# FSShield.net
KiCad netlist of a schematic drawn in EAGLE
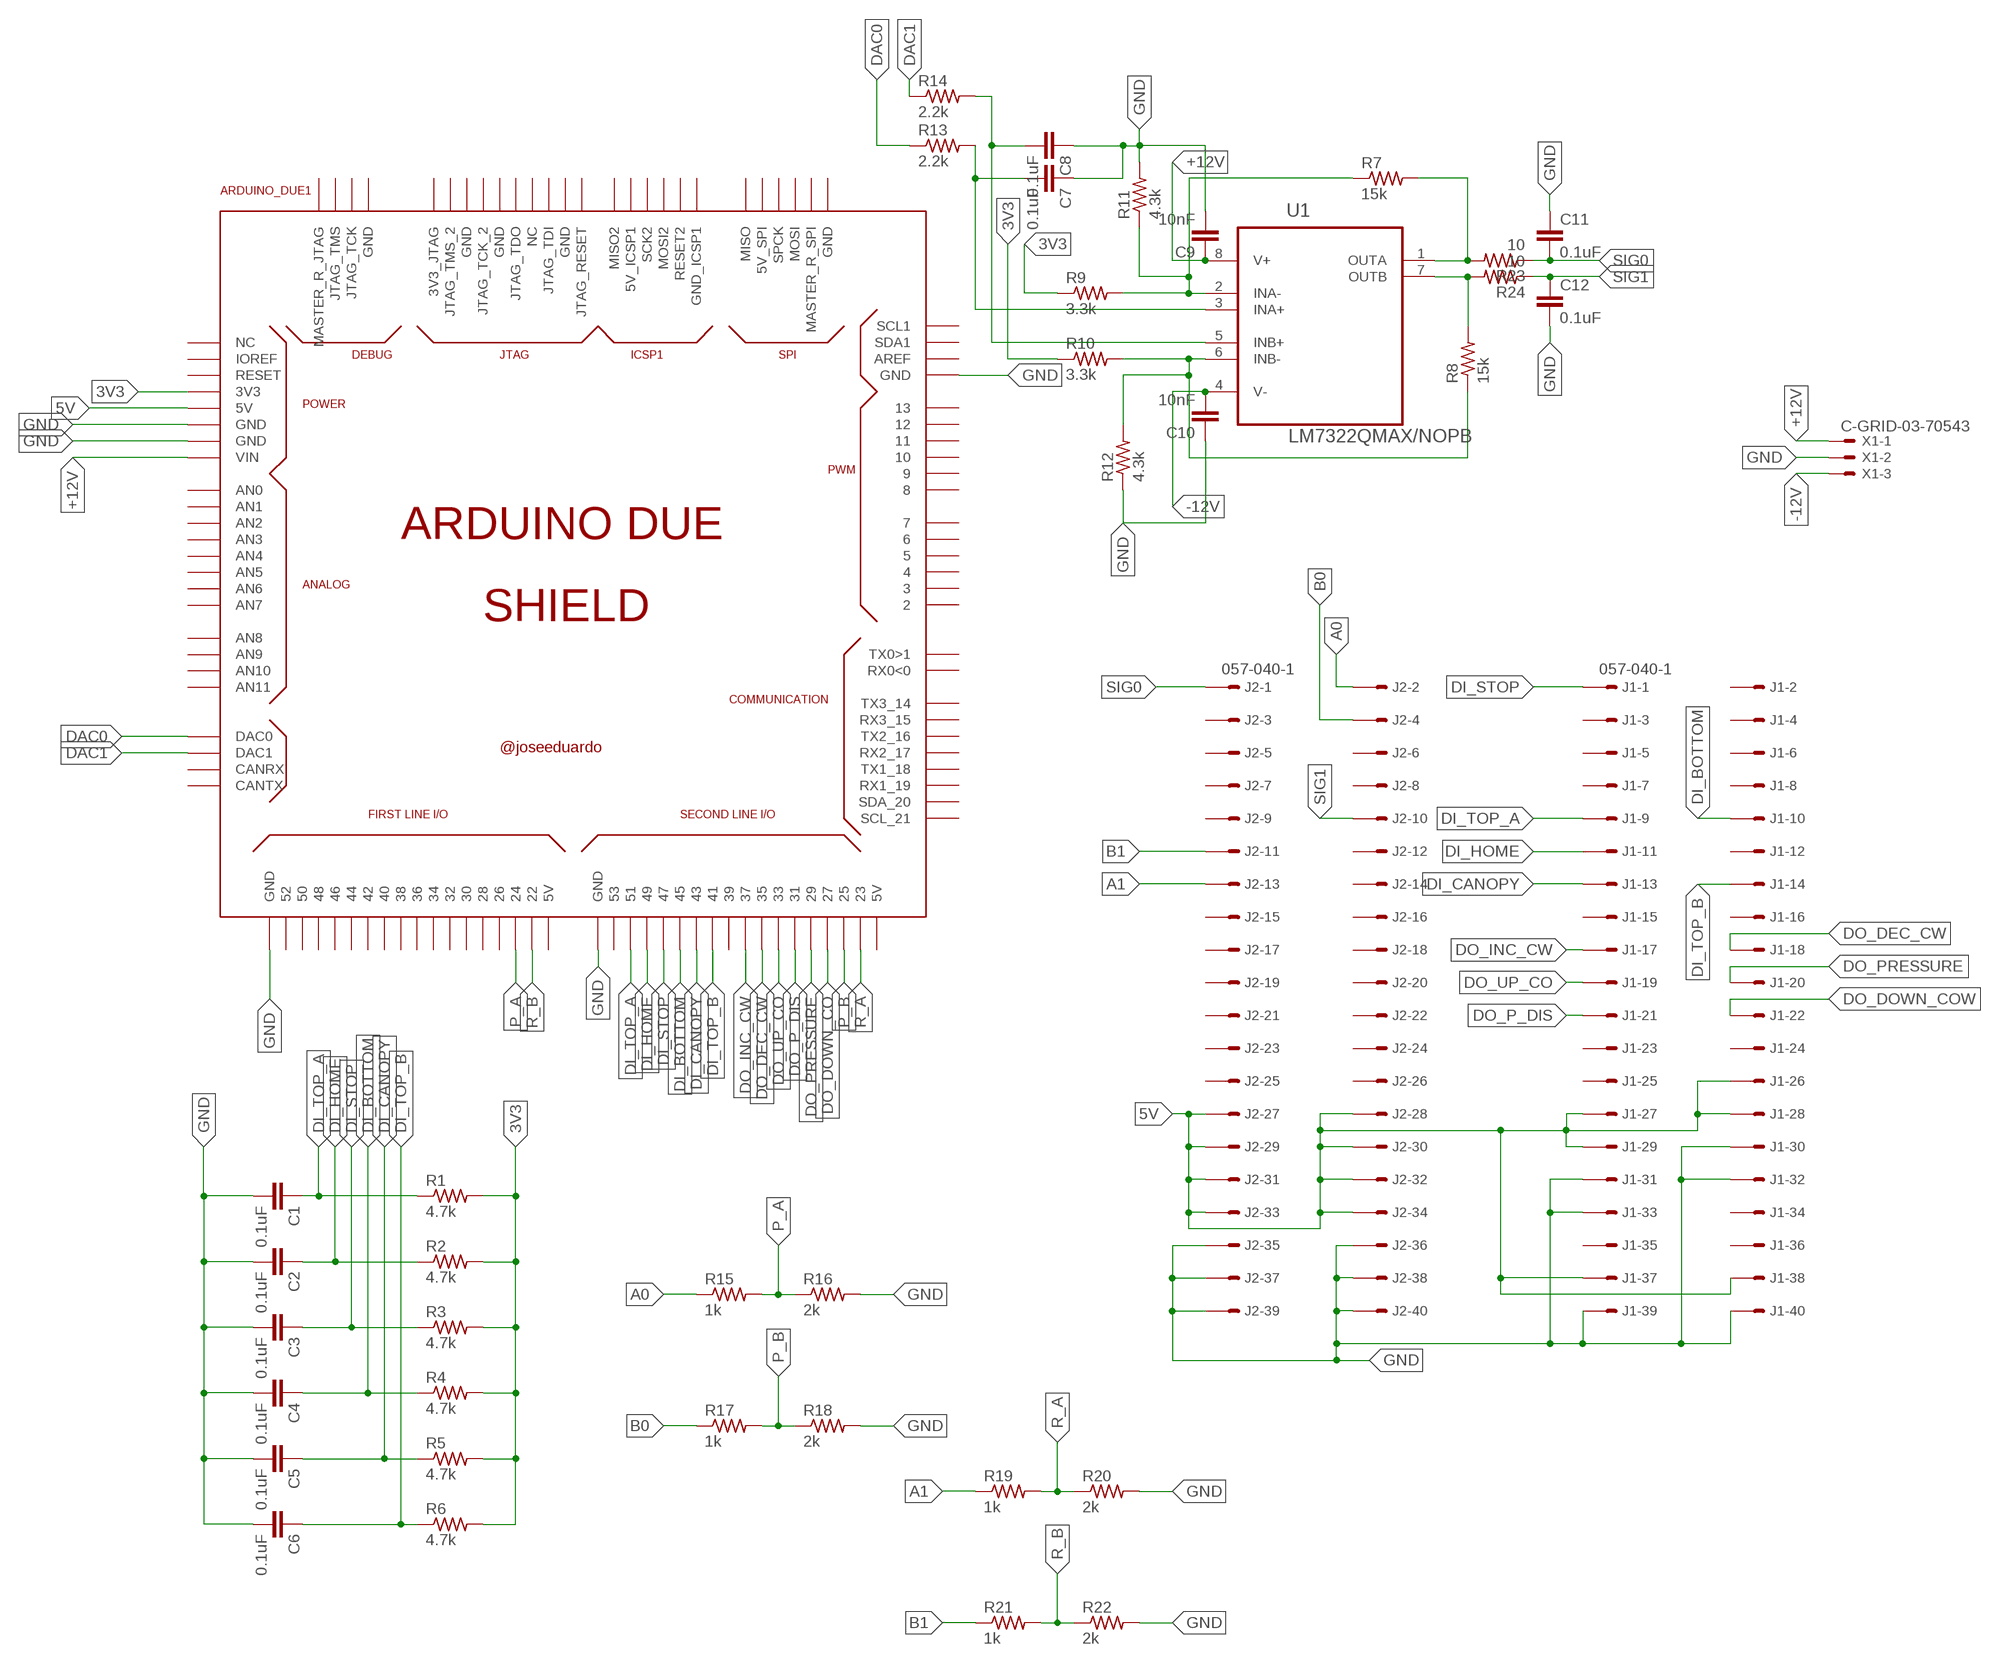
[diagram p0: schematic, sheet 1]

(export (version "E")
  (design (tool "Eeschema 10.0.6"))
  (components
    (comp (ref "ARDUINO_DUE1")
      (value "ARDUINO_DUE_SHIELD")
      (footprint "eagle-import:ARDUINO_DUE_SHIELD")
      (libsource (lib "eagle-import") (part "ARDUINO_DUE_SHIELD"))
    )
    (comp (ref "C1")
      (value "0.1uF")
      (footprint "eagle-import:0603")
      (libsource (lib "eagle-import") (part "0.1UF-0603-25V-(+80/-20%)"))
    )
    (comp (ref "C2")
      (value "0.1uF")
      (footprint "eagle-import:0603")
      (libsource (lib "eagle-import") (part "0.1UF-0603-25V-(+80/-20%)"))
    )
    (comp (ref "C3")
      (value "0.1uF")
      (footprint "eagle-import:0603")
      (libsource (lib "eagle-import") (part "0.1UF-0603-25V-(+80/-20%)"))
    )
    (comp (ref "C4")
      (value "0.1uF")
      (footprint "eagle-import:0603")
      (libsource (lib "eagle-import") (part "0.1UF-0603-25V-(+80/-20%)"))
    )
    (comp (ref "C5")
      (value "0.1uF")
      (footprint "eagle-import:0603")
      (libsource (lib "eagle-import") (part "0.1UF-0603-25V-(+80/-20%)"))
    )
    (comp (ref "C6")
      (value "0.1uF")
      (footprint "eagle-import:0603")
      (libsource (lib "eagle-import") (part "0.1UF-0603-25V-(+80/-20%)"))
    )
    (comp (ref "C7")
      (value "0.1uF")
      (footprint "eagle-import:0603")
      (libsource (lib "eagle-import") (part "0.1UF-0603-25V-(+80/-20%)"))
    )
    (comp (ref "C8")
      (value "0.1uF")
      (footprint "eagle-import:0603")
      (libsource (lib "eagle-import") (part "0.1UF-0603-25V-(+80/-20%)"))
    )
    (comp (ref "C9")
      (value "10nF")
      (footprint "eagle-import:0603")
      (libsource (lib "eagle-import") (part "10NF-0603-50V-10%"))
    )
    (comp (ref "C10")
      (value "10nF")
      (footprint "eagle-import:0603")
      (libsource (lib "eagle-import") (part "10NF-0603-50V-10%"))
    )
    (comp (ref "C11")
      (value "0.1uF")
      (footprint "eagle-import:0603")
      (libsource (lib "eagle-import") (part "0.1UF-0603-25V-(+80/-20%)"))
    )
    (comp (ref "C12")
      (value "0.1uF")
      (footprint "eagle-import:0603")
      (libsource (lib "eagle-import") (part "0.1UF-0603-25V-(+80/-20%)"))
    )
    (comp (ref "J1")
      (value "057-040-1")
      (footprint "eagle-import:057-040-1")
      (libsource (lib "eagle-import") (part "057-040-1"))
    )
    (comp (ref "J2")
      (value "057-040-1")
      (footprint "eagle-import:057-040-1")
      (libsource (lib "eagle-import") (part "057-040-1"))
    )
    (comp (ref "R1")
      (value "4.7k")
      (footprint "eagle-import:M0805")
      (libsource (lib "eagle-import") (part "R-US_M0805"))
    )
    (comp (ref "R2")
      (value "4.7k")
      (footprint "eagle-import:M0805")
      (libsource (lib "eagle-import") (part "R-US_M0805"))
    )
    (comp (ref "R3")
      (value "4.7k")
      (footprint "eagle-import:M0805")
      (libsource (lib "eagle-import") (part "R-US_M0805"))
    )
    (comp (ref "R4")
      (value "4.7k")
      (footprint "eagle-import:M0805")
      (libsource (lib "eagle-import") (part "R-US_M0805"))
    )
    (comp (ref "R5")
      (value "4.7k")
      (footprint "eagle-import:M0805")
      (libsource (lib "eagle-import") (part "R-US_M0805"))
    )
    (comp (ref "R6")
      (value "4.7k")
      (footprint "eagle-import:M0805")
      (libsource (lib "eagle-import") (part "R-US_M0805"))
    )
    (comp (ref "R7")
      (value "15k")
      (footprint "eagle-import:M0805")
      (libsource (lib "eagle-import") (part "R-US_M0805"))
    )
    (comp (ref "R8")
      (value "15k")
      (footprint "eagle-import:M0805")
      (libsource (lib "eagle-import") (part "R-US_M0805"))
    )
    (comp (ref "R9")
      (value "3.3k")
      (footprint "eagle-import:M0805")
      (libsource (lib "eagle-import") (part "R-US_M0805"))
    )
    (comp (ref "R10")
      (value "3.3k")
      (footprint "eagle-import:M0805")
      (libsource (lib "eagle-import") (part "R-US_M0805"))
    )
    (comp (ref "R11")
      (value "4.3k")
      (footprint "eagle-import:M0805")
      (libsource (lib "eagle-import") (part "R-US_M0805"))
    )
    (comp (ref "R12")
      (value "4.3k")
      (footprint "eagle-import:M0805")
      (libsource (lib "eagle-import") (part "R-US_M0805"))
    )
    (comp (ref "R13")
      (value "2.2k")
      (footprint "eagle-import:M0805")
      (libsource (lib "eagle-import") (part "R-US_M0805"))
    )
    (comp (ref "R14")
      (value "2.2k")
      (footprint "eagle-import:M0805")
      (libsource (lib "eagle-import") (part "R-US_M0805"))
    )
    (comp (ref "R15")
      (value "1k")
      (footprint "eagle-import:M0805")
      (libsource (lib "eagle-import") (part "R-US_M0805"))
    )
    (comp (ref "R16")
      (value "2k")
      (footprint "eagle-import:M0805")
      (libsource (lib "eagle-import") (part "R-US_M0805"))
    )
    (comp (ref "R17")
      (value "1k")
      (footprint "eagle-import:M0805")
      (libsource (lib "eagle-import") (part "R-US_M0805"))
    )
    (comp (ref "R18")
      (value "2k")
      (footprint "eagle-import:M0805")
      (libsource (lib "eagle-import") (part "R-US_M0805"))
    )
    (comp (ref "R19")
      (value "1k")
      (footprint "eagle-import:M0805")
      (libsource (lib "eagle-import") (part "R-US_M0805"))
    )
    (comp (ref "R20")
      (value "2k")
      (footprint "eagle-import:M0805")
      (libsource (lib "eagle-import") (part "R-US_M0805"))
    )
    (comp (ref "R21")
      (value "1k")
      (footprint "eagle-import:M0805")
      (libsource (lib "eagle-import") (part "R-US_M0805"))
    )
    (comp (ref "R22")
      (value "2k")
      (footprint "eagle-import:M0805")
      (libsource (lib "eagle-import") (part "R-US_M0805"))
    )
    (comp (ref "R23")
      (value "10")
      (footprint "eagle-import:M0805")
      (libsource (lib "eagle-import") (part "R-US_M0805"))
    )
    (comp (ref "R24")
      (value "10")
      (footprint "eagle-import:M0805")
      (libsource (lib "eagle-import") (part "R-US_M0805"))
    )
    (comp (ref "U1")
      (value "LM7322QMAX/NOPB")
      (footprint "eagle-import:SOIC127P600X175-8N")
      (fields (field (name "MF") "Texas Instruments"))
      (libsource (lib "eagle-import") (part "LM7322QMAX/NOPB"))
    )
    (comp (ref "X1")
      (value "C-GRID-03-70543")
      (footprint "eagle-import:70543-03")
      (fields (field (name "MF") "MOLEX"))
      (libsource (lib "eagle-import") (part "C-GRID-03-70543"))
    )
  )
  (nets
    (net (code "1") (name "+12V") (class "Default")
      (node (ref "ARDUINO_DUE1") (pin "VIN") (pinfunction "VIN_VIN") (pintype "bidirectional"))
      (node (ref "C9") (pin "1") (pinfunction "1_1") (pintype "passive"))
      (node (ref "U1") (pin "8") (pinfunction "V+_8") (pintype "power_in"))
      (node (ref "X1") (pin "1") (pinfunction "S_1") (pintype "passive"))
    )
    (net (code "2") (name "-12V") (class "Default")
      (node (ref "C10") (pin "2") (pinfunction "2_2") (pintype "passive"))
      (node (ref "U1") (pin "4") (pinfunction "V-_4") (pintype "power_in"))
      (node (ref "X1") (pin "3") (pinfunction "S_3") (pintype "passive"))
    )
    (net (code "3") (name "3V3") (class "Default")
      (node (ref "ARDUINO_DUE1") (pin "3V3") (pinfunction "3V3_3V3") (pintype "bidirectional"))
      (node (ref "R1") (pin "2") (pinfunction "2_2") (pintype "passive"))
      (node (ref "R10") (pin "1") (pinfunction "1_1") (pintype "passive"))
      (node (ref "R2") (pin "2") (pinfunction "2_2") (pintype "passive"))
      (node (ref "R3") (pin "2") (pinfunction "2_2") (pintype "passive"))
      (node (ref "R4") (pin "2") (pinfunction "2_2") (pintype "passive"))
      (node (ref "R5") (pin "2") (pinfunction "2_2") (pintype "passive"))
      (node (ref "R6") (pin "2") (pinfunction "2_2") (pintype "passive"))
      (node (ref "R9") (pin "1") (pinfunction "1_1") (pintype "passive"))
    )
    (net (code "4") (name "5V") (class "Default")
      (node (ref "ARDUINO_DUE1") (pin "5V0") (pinfunction "5V_5V0") (pintype "bidirectional"))
      (node (ref "J1") (pin "26") (pinfunction "S_26") (pintype "passive"))
      (node (ref "J1") (pin "27") (pinfunction "S_27") (pintype "passive"))
      (node (ref "J1") (pin "28") (pinfunction "S_28") (pintype "passive"))
      (node (ref "J1") (pin "29") (pinfunction "S_29") (pintype "passive"))
      (node (ref "J1") (pin "37") (pinfunction "S_37") (pintype "passive"))
      (node (ref "J1") (pin "38") (pinfunction "S_38") (pintype "passive"))
      (node (ref "J2") (pin "27") (pinfunction "S_27") (pintype "passive"))
      (node (ref "J2") (pin "28") (pinfunction "S_28") (pintype "passive"))
      (node (ref "J2") (pin "29") (pinfunction "S_29") (pintype "passive"))
      (node (ref "J2") (pin "30") (pinfunction "S_30") (pintype "passive"))
      (node (ref "J2") (pin "31") (pinfunction "S_31") (pintype "passive"))
      (node (ref "J2") (pin "32") (pinfunction "S_32") (pintype "passive"))
      (node (ref "J2") (pin "33") (pinfunction "S_33") (pintype "passive"))
      (node (ref "J2") (pin "34") (pinfunction "S_34") (pintype "passive"))
    )
    (net (code "5") (name "A0") (class "Default")
      (node (ref "J2") (pin "2") (pinfunction "S_2") (pintype "passive"))
      (node (ref "R15") (pin "1") (pinfunction "1_1") (pintype "passive"))
    )
    (net (code "6") (name "A1") (class "Default")
      (node (ref "J2") (pin "13") (pinfunction "S_13") (pintype "passive"))
      (node (ref "R19") (pin "1") (pinfunction "1_1") (pintype "passive"))
    )
    (net (code "7") (name "B0") (class "Default")
      (node (ref "J2") (pin "4") (pinfunction "S_4") (pintype "passive"))
      (node (ref "R17") (pin "1") (pinfunction "1_1") (pintype "passive"))
    )
    (net (code "8") (name "B1") (class "Default")
      (node (ref "J2") (pin "11") (pinfunction "S_11") (pintype "passive"))
      (node (ref "R21") (pin "1") (pinfunction "1_1") (pintype "passive"))
    )
    (net (code "9") (name "DAC0") (class "Default")
      (node (ref "ARDUINO_DUE1") (pin "DAC0") (pinfunction "DAC0_DAC0") (pintype "bidirectional"))
      (node (ref "R13") (pin "1") (pinfunction "1_1") (pintype "passive"))
    )
    (net (code "10") (name "DAC1") (class "Default")
      (node (ref "ARDUINO_DUE1") (pin "DAC1") (pinfunction "DAC1_DAC1") (pintype "bidirectional"))
      (node (ref "R14") (pin "1") (pinfunction "1_1") (pintype "passive"))
    )
    (net (code "11") (name "DI_BOTTOM") (class "Default")
      (node (ref "ARDUINO_DUE1") (pin "45") (pinfunction "45_45") (pintype "bidirectional"))
      (node (ref "C4") (pin "1") (pinfunction "1_1") (pintype "passive"))
      (node (ref "J1") (pin "10") (pinfunction "S_10") (pintype "passive"))
      (node (ref "R4") (pin "1") (pinfunction "1_1") (pintype "passive"))
    )
    (net (code "12") (name "DI_CANOPY") (class "Default")
      (node (ref "ARDUINO_DUE1") (pin "43") (pinfunction "43_43") (pintype "bidirectional"))
      (node (ref "C5") (pin "1") (pinfunction "1_1") (pintype "passive"))
      (node (ref "J1") (pin "13") (pinfunction "S_13") (pintype "passive"))
      (node (ref "R5") (pin "1") (pinfunction "1_1") (pintype "passive"))
    )
    (net (code "13") (name "DI_HOME") (class "Default")
      (node (ref "ARDUINO_DUE1") (pin "49") (pinfunction "49_49") (pintype "bidirectional"))
      (node (ref "C2") (pin "1") (pinfunction "1_1") (pintype "passive"))
      (node (ref "J1") (pin "11") (pinfunction "S_11") (pintype "passive"))
      (node (ref "R2") (pin "1") (pinfunction "1_1") (pintype "passive"))
    )
    (net (code "14") (name "DI_STOP") (class "Default")
      (node (ref "ARDUINO_DUE1") (pin "47") (pinfunction "47_47") (pintype "bidirectional"))
      (node (ref "C3") (pin "1") (pinfunction "1_1") (pintype "passive"))
      (node (ref "J1") (pin "1") (pinfunction "S_1") (pintype "passive"))
      (node (ref "R3") (pin "1") (pinfunction "1_1") (pintype "passive"))
    )
    (net (code "15") (name "DI_TOP_A") (class "Default")
      (node (ref "ARDUINO_DUE1") (pin "51") (pinfunction "51_51") (pintype "bidirectional"))
      (node (ref "C1") (pin "1") (pinfunction "1_1") (pintype "passive"))
      (node (ref "J1") (pin "9") (pinfunction "S_9") (pintype "passive"))
      (node (ref "R1") (pin "1") (pinfunction "1_1") (pintype "passive"))
    )
    (net (code "16") (name "DI_TOP_B") (class "Default")
      (node (ref "ARDUINO_DUE1") (pin "41") (pinfunction "41_41") (pintype "bidirectional"))
      (node (ref "C6") (pin "1") (pinfunction "1_1") (pintype "passive"))
      (node (ref "J1") (pin "14") (pinfunction "S_14") (pintype "passive"))
      (node (ref "R6") (pin "1") (pinfunction "1_1") (pintype "passive"))
    )
    (net (code "17") (name "DO_DEC_CW") (class "Default")
      (node (ref "ARDUINO_DUE1") (pin "35") (pinfunction "35_35") (pintype "bidirectional"))
      (node (ref "J1") (pin "18") (pinfunction "S_18") (pintype "passive"))
    )
    (net (code "18") (name "DO_DOWN_CO") (class "Default")
      (node (ref "ARDUINO_DUE1") (pin "27") (pinfunction "27_27") (pintype "bidirectional"))
    )
    (net (code "19") (name "DO_DOWN_COW") (class "Default")
      (node (ref "J1") (pin "22") (pinfunction "S_22") (pintype "passive"))
    )
    (net (code "20") (name "DO_INC_CW") (class "Default")
      (node (ref "ARDUINO_DUE1") (pin "37") (pinfunction "37_37") (pintype "bidirectional"))
      (node (ref "J1") (pin "17") (pinfunction "S_17") (pintype "passive"))
    )
    (net (code "21") (name "DO_PRESSURE") (class "Default")
      (node (ref "ARDUINO_DUE1") (pin "29") (pinfunction "29_29") (pintype "bidirectional"))
      (node (ref "J1") (pin "20") (pinfunction "S_20") (pintype "passive"))
    )
    (net (code "22") (name "DO_P_DIS") (class "Default")
      (node (ref "ARDUINO_DUE1") (pin "31") (pinfunction "31_31") (pintype "bidirectional"))
      (node (ref "J1") (pin "21") (pinfunction "S_21") (pintype "passive"))
    )
    (net (code "23") (name "DO_UP_CO") (class "Default")
      (node (ref "ARDUINO_DUE1") (pin "33") (pinfunction "33_33") (pintype "bidirectional"))
      (node (ref "J1") (pin "19") (pinfunction "S_19") (pintype "passive"))
    )
    (net (code "24") (name "GND") (class "Default")
      (node (ref "ARDUINO_DUE1") (pin "GND") (pinfunction "GND_GND") (pintype "bidirectional"))
      (node (ref "ARDUINO_DUE1") (pin "GND_1") (pinfunction "GND_GND_1") (pintype "bidirectional"))
      (node (ref "ARDUINO_DUE1") (pin "GND_2") (pinfunction "GND_GND_2") (pintype "bidirectional"))
      (node (ref "ARDUINO_DUE1") (pin "GND_3") (pinfunction "GND_GND_3") (pintype "bidirectional"))
      (node (ref "ARDUINO_DUE1") (pin "GND_4") (pinfunction "GND_GND_4") (pintype "bidirectional"))
      (node (ref "C1") (pin "2") (pinfunction "2_2") (pintype "passive"))
      (node (ref "C10") (pin "1") (pinfunction "1_1") (pintype "passive"))
      (node (ref "C11") (pin "1") (pinfunction "1_1") (pintype "passive"))
      (node (ref "C12") (pin "2") (pinfunction "2_2") (pintype "passive"))
      (node (ref "C2") (pin "2") (pinfunction "2_2") (pintype "passive"))
      (node (ref "C3") (pin "2") (pinfunction "2_2") (pintype "passive"))
      (node (ref "C4") (pin "2") (pinfunction "2_2") (pintype "passive"))
      (node (ref "C5") (pin "2") (pinfunction "2_2") (pintype "passive"))
      (node (ref "C6") (pin "2") (pinfunction "2_2") (pintype "passive"))
      (node (ref "C7") (pin "1") (pinfunction "1_1") (pintype "passive"))
      (node (ref "C8") (pin "1") (pinfunction "1_1") (pintype "passive"))
      (node (ref "C9") (pin "2") (pinfunction "2_2") (pintype "passive"))
      (node (ref "J1") (pin "30") (pinfunction "S_30") (pintype "passive"))
      (node (ref "J1") (pin "31") (pinfunction "S_31") (pintype "passive"))
      (node (ref "J1") (pin "32") (pinfunction "S_32") (pintype "passive"))
      (node (ref "J1") (pin "33") (pinfunction "S_33") (pintype "passive"))
      (node (ref "J1") (pin "39") (pinfunction "S_39") (pintype "passive"))
      (node (ref "J1") (pin "40") (pinfunction "S_40") (pintype "passive"))
      (node (ref "J2") (pin "35") (pinfunction "S_35") (pintype "passive"))
      (node (ref "J2") (pin "36") (pinfunction "S_36") (pintype "passive"))
      (node (ref "J2") (pin "37") (pinfunction "S_37") (pintype "passive"))
      (node (ref "J2") (pin "38") (pinfunction "S_38") (pintype "passive"))
      (node (ref "J2") (pin "39") (pinfunction "S_39") (pintype "passive"))
      (node (ref "J2") (pin "40") (pinfunction "S_40") (pintype "passive"))
      (node (ref "R11") (pin "2") (pinfunction "2_2") (pintype "passive"))
      (node (ref "R12") (pin "1") (pinfunction "1_1") (pintype "passive"))
      (node (ref "R16") (pin "2") (pinfunction "2_2") (pintype "passive"))
      (node (ref "R18") (pin "2") (pinfunction "2_2") (pintype "passive"))
      (node (ref "R20") (pin "2") (pinfunction "2_2") (pintype "passive"))
      (node (ref "R22") (pin "2") (pinfunction "2_2") (pintype "passive"))
      (node (ref "X1") (pin "2") (pinfunction "S_2") (pintype "passive"))
    )
    (net (code "25") (name "Net-(C11-Pad2)") (class "Default")
      (node (ref "C11") (pin "2") (pinfunction "2_2") (pintype "passive"))
      (node (ref "R23") (pin "1") (pinfunction "1_1") (pintype "passive"))
    )
    (net (code "26") (name "Net-(C12-Pad1)") (class "Default")
      (node (ref "C12") (pin "1") (pinfunction "1_1") (pintype "passive"))
      (node (ref "R24") (pin "1") (pinfunction "1_1") (pintype "passive"))
    )
    (net (code "27") (name "Net-(U1-INA+)") (class "Default")
      (node (ref "C7") (pin "2") (pinfunction "2_2") (pintype "passive"))
      (node (ref "R13") (pin "2") (pinfunction "2_2") (pintype "passive"))
      (node (ref "U1") (pin "3") (pinfunction "INA+_3") (pintype "input"))
    )
    (net (code "28") (name "Net-(U1-INA-)") (class "Default")
      (node (ref "R11") (pin "1") (pinfunction "1_1") (pintype "passive"))
      (node (ref "R7") (pin "1") (pinfunction "1_1") (pintype "passive"))
      (node (ref "R9") (pin "2") (pinfunction "2_2") (pintype "passive"))
      (node (ref "U1") (pin "2") (pinfunction "INA-_2") (pintype "input"))
    )
    (net (code "29") (name "Net-(U1-INB+)") (class "Default")
      (node (ref "C8") (pin "2") (pinfunction "2_2") (pintype "passive"))
      (node (ref "R14") (pin "2") (pinfunction "2_2") (pintype "passive"))
      (node (ref "U1") (pin "5") (pinfunction "INB+_5") (pintype "input"))
    )
    (net (code "30") (name "Net-(U1-INB-)") (class "Default")
      (node (ref "R10") (pin "2") (pinfunction "2_2") (pintype "passive"))
      (node (ref "R12") (pin "2") (pinfunction "2_2") (pintype "passive"))
      (node (ref "R8") (pin "1") (pinfunction "1_1") (pintype "passive"))
      (node (ref "U1") (pin "6") (pinfunction "INB-_6") (pintype "input"))
    )
    (net (code "31") (name "P_A") (class "Default")
      (node (ref "ARDUINO_DUE1") (pin "24") (pinfunction "24_24") (pintype "bidirectional"))
      (node (ref "R15") (pin "2") (pinfunction "2_2") (pintype "passive"))
      (node (ref "R16") (pin "1") (pinfunction "1_1") (pintype "passive"))
    )
    (net (code "32") (name "P_B") (class "Default")
      (node (ref "ARDUINO_DUE1") (pin "25") (pinfunction "25_25") (pintype "bidirectional"))
      (node (ref "R17") (pin "2") (pinfunction "2_2") (pintype "passive"))
      (node (ref "R18") (pin "1") (pinfunction "1_1") (pintype "passive"))
    )
    (net (code "33") (name "R_A") (class "Default")
      (node (ref "ARDUINO_DUE1") (pin "23") (pinfunction "23_23") (pintype "bidirectional"))
      (node (ref "R19") (pin "2") (pinfunction "2_2") (pintype "passive"))
      (node (ref "R20") (pin "1") (pinfunction "1_1") (pintype "passive"))
    )
    (net (code "34") (name "R_B") (class "Default")
      (node (ref "ARDUINO_DUE1") (pin "22") (pinfunction "22_22") (pintype "bidirectional"))
      (node (ref "R21") (pin "2") (pinfunction "2_2") (pintype "passive"))
      (node (ref "R22") (pin "1") (pinfunction "1_1") (pintype "passive"))
    )
    (net (code "35") (name "SIG0") (class "Default")
      (node (ref "J2") (pin "1") (pinfunction "S_1") (pintype "passive"))
      (node (ref "R23") (pin "2") (pinfunction "2_2") (pintype "passive"))
      (node (ref "R7") (pin "2") (pinfunction "2_2") (pintype "passive"))
      (node (ref "U1") (pin "1") (pinfunction "OUTA_1") (pintype "output"))
    )
    (net (code "36") (name "SIG1") (class "Default")
      (node (ref "J2") (pin "10") (pinfunction "S_10") (pintype "passive"))
      (node (ref "R24") (pin "2") (pinfunction "2_2") (pintype "passive"))
      (node (ref "R8") (pin "2") (pinfunction "2_2") (pintype "passive"))
      (node (ref "U1") (pin "7") (pinfunction "OUTB_7") (pintype "output"))
    )
    (net (code "37") (name "unconnected-(ARDUINO_DUE1-5V-Pad5V0_1)") (class "Default")
      (node (ref "ARDUINO_DUE1") (pin "5V0_1") (pinfunction "5V_5V0_1") (pintype "bidirectional"))
    )
    (net (code "38") (name "unconnected-(ARDUINO_DUE1-5V-Pad5V0_2)") (class "Default")
      (node (ref "ARDUINO_DUE1") (pin "5V0_2") (pinfunction "5V_5V0_2") (pintype "bidirectional"))
    )
    (net (code "39") (name "unconnected-(ARDUINO_DUE1-5V_SPI-Pad5V_2)") (class "Default")
      (node (ref "ARDUINO_DUE1") (pin "5V_2") (pinfunction "5V_SPI_5V_2") (pintype "bidirectional"))
    )
    (net (code "40") (name "unconnected-(ARDUINO_DUE1-AN0-PadA0)") (class "Default")
      (node (ref "ARDUINO_DUE1") (pin "A0") (pinfunction "AN0_A0") (pintype "bidirectional"))
    )
    (net (code "41") (name "unconnected-(ARDUINO_DUE1-AN1-PadA1)") (class "Default")
      (node (ref "ARDUINO_DUE1") (pin "A1") (pinfunction "AN1_A1") (pintype "bidirectional"))
    )
    (net (code "42") (name "unconnected-(ARDUINO_DUE1-AN2-PadA2)") (class "Default")
      (node (ref "ARDUINO_DUE1") (pin "A2") (pinfunction "AN2_A2") (pintype "bidirectional"))
    )
    (net (code "43") (name "unconnected-(ARDUINO_DUE1-AN3-PadA3)") (class "Default")
      (node (ref "ARDUINO_DUE1") (pin "A3") (pinfunction "AN3_A3") (pintype "bidirectional"))
    )
    (net (code "44") (name "unconnected-(ARDUINO_DUE1-AN4-PadA4)") (class "Default")
      (node (ref "ARDUINO_DUE1") (pin "A4") (pinfunction "AN4_A4") (pintype "bidirectional"))
    )
    (net (code "45") (name "unconnected-(ARDUINO_DUE1-AN5-PadA5)") (class "Default")
      (node (ref "ARDUINO_DUE1") (pin "A5") (pinfunction "AN5_A5") (pintype "bidirectional"))
    )
    (net (code "46") (name "unconnected-(ARDUINO_DUE1-AN6-PadA6)") (class "Default")
      (node (ref "ARDUINO_DUE1") (pin "A6") (pinfunction "AN6_A6") (pintype "bidirectional"))
    )
    (net (code "47") (name "unconnected-(ARDUINO_DUE1-AN7-PadA7)") (class "Default")
      (node (ref "ARDUINO_DUE1") (pin "A7") (pinfunction "AN7_A7") (pintype "bidirectional"))
    )
    (net (code "48") (name "unconnected-(ARDUINO_DUE1-AN8-PadA8)") (class "Default")
      (node (ref "ARDUINO_DUE1") (pin "A8") (pinfunction "AN8_A8") (pintype "bidirectional"))
    )
    (net (code "49") (name "unconnected-(ARDUINO_DUE1-AN9-PadA9)") (class "Default")
      (node (ref "ARDUINO_DUE1") (pin "A9") (pinfunction "AN9_A9") (pintype "bidirectional"))
    )
    (net (code "50") (name "unconnected-(ARDUINO_DUE1-AN10-PadA10)") (class "Default")
      (node (ref "ARDUINO_DUE1") (pin "A10") (pinfunction "AN10_A10") (pintype "bidirectional"))
    )
    (net (code "51") (name "unconnected-(ARDUINO_DUE1-AN11-PadA11)") (class "Default")
      (node (ref "ARDUINO_DUE1") (pin "A11") (pinfunction "AN11_A11") (pintype "bidirectional"))
    )
    (net (code "52") (name "unconnected-(ARDUINO_DUE1-GND-PadGND_5)") (class "Default")
      (node (ref "ARDUINO_DUE1") (pin "GND_5") (pinfunction "GND_GND_5") (pintype "bidirectional"))
    )
    (net (code "53") (name "unconnected-(ARDUINO_DUE1-GND-PadGND_7)") (class "Default")
      (node (ref "ARDUINO_DUE1") (pin "GND_7") (pinfunction "GND_GND_7") (pintype "bidirectional"))
    )
    (net (code "54") (name "unconnected-(ARDUINO_DUE1-GND-PadGND_8)") (class "Default")
      (node (ref "ARDUINO_DUE1") (pin "GND_8") (pinfunction "GND_GND_8") (pintype "bidirectional"))
    )
    (net (code "55") (name "unconnected-(ARDUINO_DUE1-GND-PadGND_9)") (class "Default")
      (node (ref "ARDUINO_DUE1") (pin "GND_9") (pinfunction "GND_GND_9") (pintype "bidirectional"))
    )
    (net (code "56") (name "unconnected-(ARDUINO_DUE1-GND-PadGND_10)") (class "Default")
      (node (ref "ARDUINO_DUE1") (pin "GND_10") (pinfunction "GND_GND_10") (pintype "bidirectional"))
    )
    (net (code "57") (name "unconnected-(ARDUINO_DUE1-MASTER_R_JTAG-PadMASTER_RESET_JTAG)") (class "Default")
      (node (ref "ARDUINO_DUE1") (pin "MASTER_RESET_JTAG") (pinfunction "MASTER_R_JTAG_MASTER_RESET_JTAG") (pintype "bidirectional"))
    )
    (net (code "58") (name "unconnected-(ARDUINO_DUE1-MASTER_R_SPI-PadMASTER_RESET_SPI)") (class "Default")
      (node (ref "ARDUINO_DUE1") (pin "MASTER_RESET_SPI") (pinfunction "MASTER_R_SPI_MASTER_RESET_SPI") (pintype "bidirectional"))
    )
    (net (code "59") (name "unconnected-(ARDUINO_DUE1-NC-PadNC_2)") (class "Default")
      (node (ref "ARDUINO_DUE1") (pin "NC_2") (pinfunction "NC_NC_2") (pintype "no_connect"))
    )
    (net (code "60") (name "unconnected-(ARDUINO_DUE1-NC-PadNC_5)") (class "Default")
      (node (ref "ARDUINO_DUE1") (pin "NC_5") (pinfunction "NC_NC_5") (pintype "bidirectional"))
    )
    (net (code "61") (name "unconnected-(ARDUINO_DUE1-Pad2)") (class "Default")
      (node (ref "ARDUINO_DUE1") (pin "2") (pinfunction "2_2") (pintype "bidirectional"))
    )
    (net (code "62") (name "unconnected-(ARDUINO_DUE1-Pad3)") (class "Default")
      (node (ref "ARDUINO_DUE1") (pin "3") (pinfunction "3_3") (pintype "bidirectional"))
    )
    (net (code "63") (name "unconnected-(ARDUINO_DUE1-Pad3V3_JTAG)") (class "Default")
      (node (ref "ARDUINO_DUE1") (pin "3V3_JTAG") (pinfunction "3V3_JTAG_3V3_JTAG") (pintype "bidirectional"))
    )
    (net (code "64") (name "unconnected-(ARDUINO_DUE1-Pad4)") (class "Default")
      (node (ref "ARDUINO_DUE1") (pin "4") (pinfunction "4_4") (pintype "bidirectional"))
    )
    (net (code "65") (name "unconnected-(ARDUINO_DUE1-Pad5)") (class "Default")
      (node (ref "ARDUINO_DUE1") (pin "5") (pinfunction "5_5") (pintype "bidirectional"))
    )
    (net (code "66") (name "unconnected-(ARDUINO_DUE1-Pad5V_ICSP1)") (class "Default")
      (node (ref "ARDUINO_DUE1") (pin "5V_ICSP1") (pinfunction "5V_ICSP1_5V_ICSP1") (pintype "bidirectional"))
    )
    (net (code "67") (name "unconnected-(ARDUINO_DUE1-Pad6)") (class "Default")
      (node (ref "ARDUINO_DUE1") (pin "6") (pinfunction "6_6") (pintype "bidirectional"))
    )
    (net (code "68") (name "unconnected-(ARDUINO_DUE1-Pad7)") (class "Default")
      (node (ref "ARDUINO_DUE1") (pin "7") (pinfunction "7_7") (pintype "bidirectional"))
    )
    (net (code "69") (name "unconnected-(ARDUINO_DUE1-Pad8)") (class "Default")
      (node (ref "ARDUINO_DUE1") (pin "8") (pinfunction "8_8") (pintype "bidirectional"))
    )
    (net (code "70") (name "unconnected-(ARDUINO_DUE1-Pad9)") (class "Default")
      (node (ref "ARDUINO_DUE1") (pin "9") (pinfunction "9_9") (pintype "bidirectional"))
    )
    (net (code "71") (name "unconnected-(ARDUINO_DUE1-Pad10)") (class "Default")
      (node (ref "ARDUINO_DUE1") (pin "10") (pinfunction "10_10") (pintype "bidirectional"))
    )
    (net (code "72") (name "unconnected-(ARDUINO_DUE1-Pad11)") (class "Default")
      (node (ref "ARDUINO_DUE1") (pin "11") (pinfunction "11_11") (pintype "bidirectional"))
    )
    (net (code "73") (name "unconnected-(ARDUINO_DUE1-Pad12)") (class "Default")
      (node (ref "ARDUINO_DUE1") (pin "12") (pinfunction "12_12") (pintype "bidirectional"))
    )
    (net (code "74") (name "unconnected-(ARDUINO_DUE1-Pad13)") (class "Default")
      (node (ref "ARDUINO_DUE1") (pin "13") (pinfunction "13_13") (pintype "bidirectional"))
    )
    (net (code "75") (name "unconnected-(ARDUINO_DUE1-Pad26)") (class "Default")
      (node (ref "ARDUINO_DUE1") (pin "26") (pinfunction "26_26") (pintype "bidirectional"))
    )
    (net (code "76") (name "unconnected-(ARDUINO_DUE1-Pad28)") (class "Default")
      (node (ref "ARDUINO_DUE1") (pin "28") (pinfunction "28_28") (pintype "bidirectional"))
    )
    (net (code "77") (name "unconnected-(ARDUINO_DUE1-Pad30)") (class "Default")
      (node (ref "ARDUINO_DUE1") (pin "30") (pinfunction "30_30") (pintype "bidirectional"))
    )
    (net (code "78") (name "unconnected-(ARDUINO_DUE1-Pad32)") (class "Default")
      (node (ref "ARDUINO_DUE1") (pin "32") (pinfunction "32_32") (pintype "bidirectional"))
    )
    (net (code "79") (name "unconnected-(ARDUINO_DUE1-Pad34)") (class "Default")
      (node (ref "ARDUINO_DUE1") (pin "34") (pinfunction "34_34") (pintype "bidirectional"))
    )
    (net (code "80") (name "unconnected-(ARDUINO_DUE1-Pad36)") (class "Default")
      (node (ref "ARDUINO_DUE1") (pin "36") (pinfunction "36_36") (pintype "bidirectional"))
    )
    (net (code "81") (name "unconnected-(ARDUINO_DUE1-Pad38)") (class "Default")
      (node (ref "ARDUINO_DUE1") (pin "38") (pinfunction "38_38") (pintype "bidirectional"))
    )
    (net (code "82") (name "unconnected-(ARDUINO_DUE1-Pad39)") (class "Default")
      (node (ref "ARDUINO_DUE1") (pin "39") (pinfunction "39_39") (pintype "bidirectional"))
    )
    (net (code "83") (name "unconnected-(ARDUINO_DUE1-Pad40)") (class "Default")
      (node (ref "ARDUINO_DUE1") (pin "40") (pinfunction "40_40") (pintype "bidirectional"))
    )
    (net (code "84") (name "unconnected-(ARDUINO_DUE1-Pad42)") (class "Default")
      (node (ref "ARDUINO_DUE1") (pin "42") (pinfunction "42_42") (pintype "bidirectional"))
    )
    (net (code "85") (name "unconnected-(ARDUINO_DUE1-Pad44)") (class "Default")
      (node (ref "ARDUINO_DUE1") (pin "44") (pinfunction "44_44") (pintype "bidirectional"))
    )
    (net (code "86") (name "unconnected-(ARDUINO_DUE1-Pad46)") (class "Default")
      (node (ref "ARDUINO_DUE1") (pin "46") (pinfunction "46_46") (pintype "bidirectional"))
    )
    (net (code "87") (name "unconnected-(ARDUINO_DUE1-Pad48)") (class "Default")
      (node (ref "ARDUINO_DUE1") (pin "48") (pinfunction "48_48") (pintype "bidirectional"))
    )
    (net (code "88") (name "unconnected-(ARDUINO_DUE1-Pad50)") (class "Default")
      (node (ref "ARDUINO_DUE1") (pin "50") (pinfunction "50_50") (pintype "bidirectional"))
    )
    (net (code "89") (name "unconnected-(ARDUINO_DUE1-Pad52)") (class "Default")
      (node (ref "ARDUINO_DUE1") (pin "52") (pinfunction "52_52") (pintype "bidirectional"))
    )
    (net (code "90") (name "unconnected-(ARDUINO_DUE1-Pad53)") (class "Default")
      (node (ref "ARDUINO_DUE1") (pin "53") (pinfunction "53_53") (pintype "bidirectional"))
    )
    (net (code "91") (name "unconnected-(ARDUINO_DUE1-PadAREF)") (class "Default")
      (node (ref "ARDUINO_DUE1") (pin "AREF") (pinfunction "AREF_AREF") (pintype "bidirectional"))
    )
    (net (code "92") (name "unconnected-(ARDUINO_DUE1-PadCANRX)") (class "Default")
      (node (ref "ARDUINO_DUE1") (pin "CANRX") (pinfunction "CANRX_CANRX") (pintype "bidirectional"))
    )
    (net (code "93") (name "unconnected-(ARDUINO_DUE1-PadCANTX)") (class "Default")
      (node (ref "ARDUINO_DUE1") (pin "CANTX") (pinfunction "CANTX_CANTX") (pintype "bidirectional"))
    )
    (net (code "94") (name "unconnected-(ARDUINO_DUE1-PadGND_ICSP1)") (class "Default")
      (node (ref "ARDUINO_DUE1") (pin "GND_ICSP1") (pinfunction "GND_ICSP1_GND_ICSP1") (pintype "bidirectional"))
    )
    (net (code "95") (name "unconnected-(ARDUINO_DUE1-PadIOREF)") (class "Default")
      (node (ref "ARDUINO_DUE1") (pin "IOREF") (pinfunction "IOREF_IOREF") (pintype "bidirectional"))
    )
    (net (code "96") (name "unconnected-(ARDUINO_DUE1-PadJTAG_RESET)") (class "Default")
      (node (ref "ARDUINO_DUE1") (pin "JTAG_RESET") (pinfunction "JTAG_RESET_JTAG_RESET") (pintype "bidirectional"))
    )
    (net (code "97") (name "unconnected-(ARDUINO_DUE1-PadJTAG_TCK)") (class "Default")
      (node (ref "ARDUINO_DUE1") (pin "JTAG_TCK") (pinfunction "JTAG_TCK_JTAG_TCK") (pintype "bidirectional"))
    )
    (net (code "98") (name "unconnected-(ARDUINO_DUE1-PadJTAG_TCK_2)") (class "Default")
      (node (ref "ARDUINO_DUE1") (pin "JTAG_TCK_2") (pinfunction "JTAG_TCK_2_JTAG_TCK_2") (pintype "bidirectional"))
    )
    (net (code "99") (name "unconnected-(ARDUINO_DUE1-PadJTAG_TDI)") (class "Default")
      (node (ref "ARDUINO_DUE1") (pin "JTAG_TDI") (pinfunction "JTAG_TDI_JTAG_TDI") (pintype "bidirectional"))
    )
    (net (code "100") (name "unconnected-(ARDUINO_DUE1-PadJTAG_TDO)") (class "Default")
      (node (ref "ARDUINO_DUE1") (pin "JTAG_TDO") (pinfunction "JTAG_TDO_JTAG_TDO") (pintype "bidirectional"))
    )
    (net (code "101") (name "unconnected-(ARDUINO_DUE1-PadJTAG_TMS)") (class "Default")
      (node (ref "ARDUINO_DUE1") (pin "JTAG_TMS") (pinfunction "JTAG_TMS_JTAG_TMS") (pintype "bidirectional"))
    )
    (net (code "102") (name "unconnected-(ARDUINO_DUE1-PadJTAG_TMS_2)") (class "Default")
      (node (ref "ARDUINO_DUE1") (pin "JTAG_TMS_2") (pinfunction "JTAG_TMS_2_JTAG_TMS_2") (pintype "bidirectional"))
    )
    (net (code "103") (name "unconnected-(ARDUINO_DUE1-PadMISO)") (class "Default")
      (node (ref "ARDUINO_DUE1") (pin "MISO") (pinfunction "MISO_MISO") (pintype "bidirectional"))
    )
    (net (code "104") (name "unconnected-(ARDUINO_DUE1-PadMISO2)") (class "Default")
      (node (ref "ARDUINO_DUE1") (pin "MISO2") (pinfunction "MISO2_MISO2") (pintype "bidirectional"))
    )
    (net (code "105") (name "unconnected-(ARDUINO_DUE1-PadMOSI)") (class "Default")
      (node (ref "ARDUINO_DUE1") (pin "MOSI") (pinfunction "MOSI_MOSI") (pintype "bidirectional"))
    )
    (net (code "106") (name "unconnected-(ARDUINO_DUE1-PadMOSI2)") (class "Default")
      (node (ref "ARDUINO_DUE1") (pin "MOSI2") (pinfunction "MOSI2_MOSI2") (pintype "bidirectional"))
    )
    (net (code "107") (name "unconnected-(ARDUINO_DUE1-PadRESET)") (class "Default")
      (node (ref "ARDUINO_DUE1") (pin "RESET") (pinfunction "RESET_RESET") (pintype "bidirectional"))
    )
    (net (code "108") (name "unconnected-(ARDUINO_DUE1-PadRESET2)") (class "Default")
      (node (ref "ARDUINO_DUE1") (pin "RESET2") (pinfunction "RESET2_RESET2") (pintype "bidirectional"))
    )
    (net (code "109") (name "unconnected-(ARDUINO_DUE1-PadSCK2)") (class "Default")
      (node (ref "ARDUINO_DUE1") (pin "SCK2") (pinfunction "SCK2_SCK2") (pintype "bidirectional"))
    )
    (net (code "110") (name "unconnected-(ARDUINO_DUE1-PadSCL1)") (class "Default")
      (node (ref "ARDUINO_DUE1") (pin "SCL1") (pinfunction "SCL1_SCL1") (pintype "bidirectional"))
    )
    (net (code "111") (name "unconnected-(ARDUINO_DUE1-PadSDA1)") (class "Default")
      (node (ref "ARDUINO_DUE1") (pin "SDA1") (pinfunction "SDA1_SDA1") (pintype "bidirectional"))
    )
    (net (code "112") (name "unconnected-(ARDUINO_DUE1-PadSPCK)") (class "Default")
      (node (ref "ARDUINO_DUE1") (pin "SPCK") (pinfunction "SPCK_SPCK") (pintype "bidirectional"))
    )
    (net (code "113") (name "unconnected-(ARDUINO_DUE1-RX0<0-Pad0)") (class "Default")
      (node (ref "ARDUINO_DUE1") (pin "0") (pinfunction "RX0<0_0") (pintype "bidirectional"))
    )
    (net (code "114") (name "unconnected-(ARDUINO_DUE1-RX1_19-Pad19)") (class "Default")
      (node (ref "ARDUINO_DUE1") (pin "19") (pinfunction "RX1_19_19") (pintype "bidirectional"))
    )
    (net (code "115") (name "unconnected-(ARDUINO_DUE1-RX2_17-Pad17)") (class "Default")
      (node (ref "ARDUINO_DUE1") (pin "17") (pinfunction "RX2_17_17") (pintype "bidirectional"))
    )
    (net (code "116") (name "unconnected-(ARDUINO_DUE1-RX3_15-Pad15)") (class "Default")
      (node (ref "ARDUINO_DUE1") (pin "15") (pinfunction "RX3_15_15") (pintype "bidirectional"))
    )
    (net (code "117") (name "unconnected-(ARDUINO_DUE1-SCL_21-Pad21)") (class "Default")
      (node (ref "ARDUINO_DUE1") (pin "21") (pinfunction "SCL_21_21") (pintype "bidirectional"))
    )
    (net (code "118") (name "unconnected-(ARDUINO_DUE1-SDA_20-Pad20)") (class "Default")
      (node (ref "ARDUINO_DUE1") (pin "20") (pinfunction "SDA_20_20") (pintype "bidirectional"))
    )
    (net (code "119") (name "unconnected-(ARDUINO_DUE1-TX0>1-Pad1)") (class "Default")
      (node (ref "ARDUINO_DUE1") (pin "1") (pinfunction "TX0>1_1") (pintype "bidirectional"))
    )
    (net (code "120") (name "unconnected-(ARDUINO_DUE1-TX1_18-Pad18)") (class "Default")
      (node (ref "ARDUINO_DUE1") (pin "18") (pinfunction "TX1_18_18") (pintype "bidirectional"))
    )
    (net (code "121") (name "unconnected-(ARDUINO_DUE1-TX2_16-Pad16)") (class "Default")
      (node (ref "ARDUINO_DUE1") (pin "16") (pinfunction "TX2_16_16") (pintype "bidirectional"))
    )
    (net (code "122") (name "unconnected-(ARDUINO_DUE1-TX3_14-Pad14)") (class "Default")
      (node (ref "ARDUINO_DUE1") (pin "14") (pinfunction "TX3_14_14") (pintype "bidirectional"))
    )
    (net (code "123") (name "unconnected-(J1AB-S-Pad34)") (class "Default")
      (node (ref "J1") (pin "34") (pinfunction "S_34") (pintype "passive"))
    )
    (net (code "124") (name "unconnected-(J1AC-S-Pad35)") (class "Default")
      (node (ref "J1") (pin "35") (pinfunction "S_35") (pintype "passive"))
    )
    (net (code "125") (name "unconnected-(J1AD-S-Pad36)") (class "Default")
      (node (ref "J1") (pin "36") (pinfunction "S_36") (pintype "passive"))
    )
    (net (code "126") (name "unconnected-(J1AH-S-Pad4)") (class "Default")
      (node (ref "J1") (pin "4") (pinfunction "S_4") (pintype "passive"))
    )
    (net (code "127") (name "unconnected-(J1AJ-S-Pad5)") (class "Default")
      (node (ref "J1") (pin "5") (pinfunction "S_5") (pintype "passive"))
    )
    (net (code "128") (name "unconnected-(J1AK-S-Pad6)") (class "Default")
      (node (ref "J1") (pin "6") (pinfunction "S_6") (pintype "passive"))
    )
    (net (code "129") (name "unconnected-(J1AL-S-Pad7)") (class "Default")
      (node (ref "J1") (pin "7") (pinfunction "S_7") (pintype "passive"))
    )
    (net (code "130") (name "unconnected-(J1AM-S-Pad8)") (class "Default")
      (node (ref "J1") (pin "8") (pinfunction "S_8") (pintype "passive"))
    )
    (net (code "131") (name "unconnected-(J1D-S-Pad12)") (class "Default")
      (node (ref "J1") (pin "12") (pinfunction "S_12") (pintype "passive"))
    )
    (net (code "132") (name "unconnected-(J1G-S-Pad15)") (class "Default")
      (node (ref "J1") (pin "15") (pinfunction "S_15") (pintype "passive"))
    )
    (net (code "133") (name "unconnected-(J1H-S-Pad16)") (class "Default")
      (node (ref "J1") (pin "16") (pinfunction "S_16") (pintype "passive"))
    )
    (net (code "134") (name "unconnected-(J1L-S-Pad2)") (class "Default")
      (node (ref "J1") (pin "2") (pinfunction "S_2") (pintype "passive"))
    )
    (net (code "135") (name "unconnected-(J1P-S-Pad23)") (class "Default")
      (node (ref "J1") (pin "23") (pinfunction "S_23") (pintype "passive"))
    )
    (net (code "136") (name "unconnected-(J1Q-S-Pad24)") (class "Default")
      (node (ref "J1") (pin "24") (pinfunction "S_24") (pintype "passive"))
    )
    (net (code "137") (name "unconnected-(J1R-S-Pad25)") (class "Default")
      (node (ref "J1") (pin "25") (pinfunction "S_25") (pintype "passive"))
    )
    (net (code "138") (name "unconnected-(J1W-S-Pad3)") (class "Default")
      (node (ref "J1") (pin "3") (pinfunction "S_3") (pintype "passive"))
    )
    (net (code "139") (name "unconnected-(J2AJ-S-Pad5)") (class "Default")
      (node (ref "J2") (pin "5") (pinfunction "S_5") (pintype "passive"))
    )
    (net (code "140") (name "unconnected-(J2AK-S-Pad6)") (class "Default")
      (node (ref "J2") (pin "6") (pinfunction "S_6") (pintype "passive"))
    )
    (net (code "141") (name "unconnected-(J2AL-S-Pad7)") (class "Default")
      (node (ref "J2") (pin "7") (pinfunction "S_7") (pintype "passive"))
    )
    (net (code "142") (name "unconnected-(J2AM-S-Pad8)") (class "Default")
      (node (ref "J2") (pin "8") (pinfunction "S_8") (pintype "passive"))
    )
    (net (code "143") (name "unconnected-(J2AN-S-Pad9)") (class "Default")
      (node (ref "J2") (pin "9") (pinfunction "S_9") (pintype "passive"))
    )
    (net (code "144") (name "unconnected-(J2D-S-Pad12)") (class "Default")
      (node (ref "J2") (pin "12") (pinfunction "S_12") (pintype "passive"))
    )
    (net (code "145") (name "unconnected-(J2F-S-Pad14)") (class "Default")
      (node (ref "J2") (pin "14") (pinfunction "S_14") (pintype "passive"))
    )
    (net (code "146") (name "unconnected-(J2G-S-Pad15)") (class "Default")
      (node (ref "J2") (pin "15") (pinfunction "S_15") (pintype "passive"))
    )
    (net (code "147") (name "unconnected-(J2H-S-Pad16)") (class "Default")
      (node (ref "J2") (pin "16") (pinfunction "S_16") (pintype "passive"))
    )
    (net (code "148") (name "unconnected-(J2I-S-Pad17)") (class "Default")
      (node (ref "J2") (pin "17") (pinfunction "S_17") (pintype "passive"))
    )
    (net (code "149") (name "unconnected-(J2J-S-Pad18)") (class "Default")
      (node (ref "J2") (pin "18") (pinfunction "S_18") (pintype "passive"))
    )
    (net (code "150") (name "unconnected-(J2K-S-Pad19)") (class "Default")
      (node (ref "J2") (pin "19") (pinfunction "S_19") (pintype "passive"))
    )
    (net (code "151") (name "unconnected-(J2M-S-Pad20)") (class "Default")
      (node (ref "J2") (pin "20") (pinfunction "S_20") (pintype "passive"))
    )
    (net (code "152") (name "unconnected-(J2N-S-Pad21)") (class "Default")
      (node (ref "J2") (pin "21") (pinfunction "S_21") (pintype "passive"))
    )
    (net (code "153") (name "unconnected-(J2O-S-Pad22)") (class "Default")
      (node (ref "J2") (pin "22") (pinfunction "S_22") (pintype "passive"))
    )
    (net (code "154") (name "unconnected-(J2P-S-Pad23)") (class "Default")
      (node (ref "J2") (pin "23") (pinfunction "S_23") (pintype "passive"))
    )
    (net (code "155") (name "unconnected-(J2Q-S-Pad24)") (class "Default")
      (node (ref "J2") (pin "24") (pinfunction "S_24") (pintype "passive"))
    )
    (net (code "156") (name "unconnected-(J2R-S-Pad25)") (class "Default")
      (node (ref "J2") (pin "25") (pinfunction "S_25") (pintype "passive"))
    )
    (net (code "157") (name "unconnected-(J2S-S-Pad26)") (class "Default")
      (node (ref "J2") (pin "26") (pinfunction "S_26") (pintype "passive"))
    )
    (net (code "158") (name "unconnected-(J2W-S-Pad3)") (class "Default")
      (node (ref "J2") (pin "3") (pinfunction "S_3") (pintype "passive"))
    )
  )
)
